# RoverBaseboard.net
KiCad netlist of a schematic drawn in EAGLE
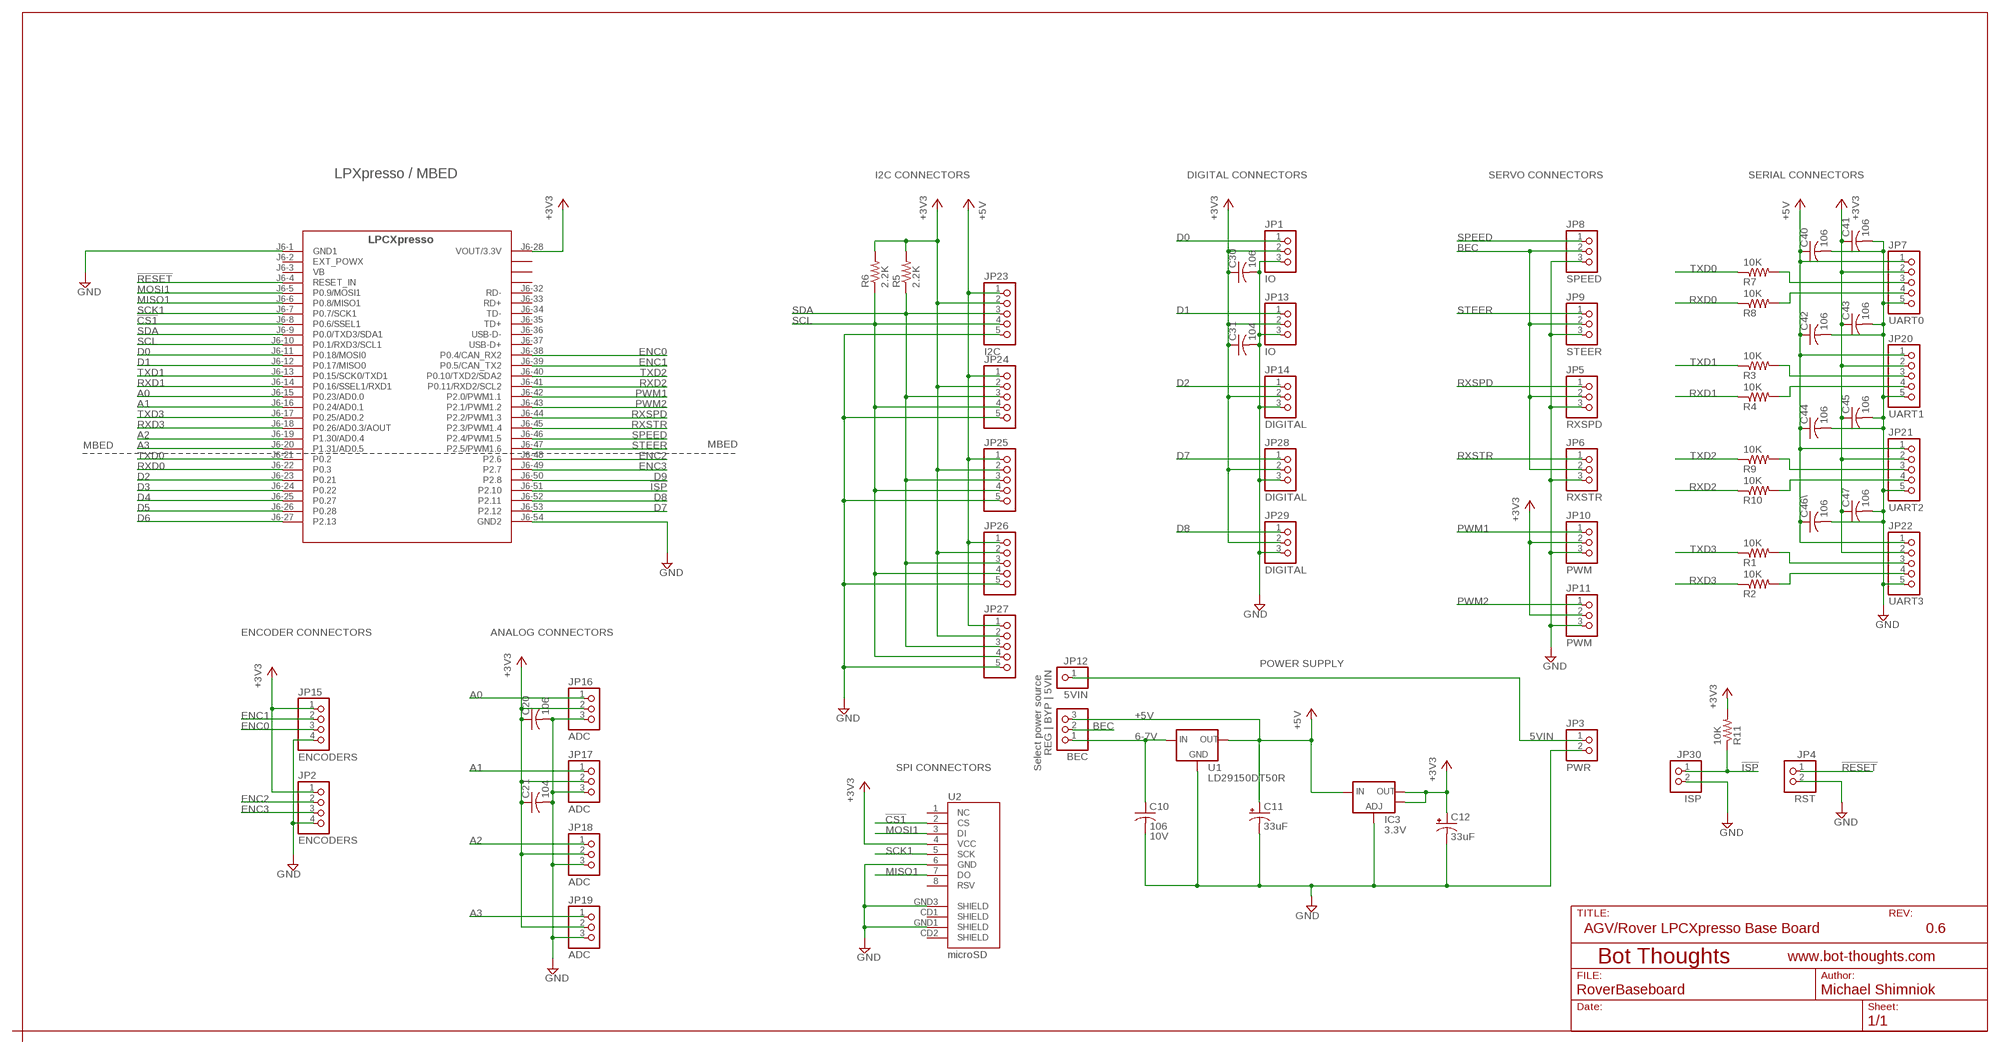
[diagram p0: schematic, sheet 1]

(export (version "E")
  (design (tool "Eeschema 10.0.6"))
  (components
    (comp (ref "BEC")
      (value "REG | BYP | 5VIN")
      (footprint "eagle-import:1X03-S")
      (libsource (lib "eagle-import") (part "PINHD-1X03_2.54-S"))
    )
    (comp (ref "C10")
      (value "106")
      (footprint "eagle-import:C1206")
      (fields (field (name "VOLTAGE") "10V"))
      (libsource (lib "eagle-import") (part "C-USC1206"))
    )
    (comp (ref "C11")
      (value "33uF")
      (footprint "eagle-import:SMC_B")
      (libsource (lib "eagle-import") (part "CPOL-USSMCB"))
    )
    (comp (ref "C12")
      (value "33uF")
      (footprint "eagle-import:SMC_B")
      (libsource (lib "eagle-import") (part "CPOL-USSMCB"))
    )
    (comp (ref "C20")
      (value "106")
      (footprint "eagle-import:C0603")
      (libsource (lib "eagle-import") (part "C-USC0603"))
    )
    (comp (ref "C21")
      (value "104")
      (footprint "eagle-import:C0603")
      (libsource (lib "eagle-import") (part "C-USC0603"))
    )
    (comp (ref "C30")
      (value "106")
      (footprint "eagle-import:C0603")
      (libsource (lib "eagle-import") (part "C-USC0603"))
    )
    (comp (ref "C31")
      (value "104")
      (footprint "eagle-import:C0603")
      (libsource (lib "eagle-import") (part "C-USC0603"))
    )
    (comp (ref "C40")
      (value "106")
      (footprint "eagle-import:C0603")
      (libsource (lib "eagle-import") (part "C-USC0603"))
    )
    (comp (ref "C41")
      (value "106")
      (footprint "eagle-import:C0603")
      (libsource (lib "eagle-import") (part "C-USC0603"))
    )
    (comp (ref "C42")
      (value "106")
      (footprint "eagle-import:C0603")
      (libsource (lib "eagle-import") (part "C-USC0603"))
    )
    (comp (ref "C43")
      (value "106")
      (footprint "eagle-import:C0603")
      (libsource (lib "eagle-import") (part "C-USC0603"))
    )
    (comp (ref "C44")
      (value "106")
      (footprint "eagle-import:C0603")
      (libsource (lib "eagle-import") (part "C-USC0603"))
    )
    (comp (ref "C45")
      (value "106")
      (footprint "eagle-import:C0603")
      (libsource (lib "eagle-import") (part "C-USC0603"))
    )
    (comp (ref "C46\\")
      (value "106")
      (footprint "eagle-import:C0603")
      (libsource (lib "eagle-import") (part "C-USC0603"))
    )
    (comp (ref "C47")
      (value "106")
      (footprint "eagle-import:C0603")
      (libsource (lib "eagle-import") (part "C-USC0603"))
    )
    (comp (ref "IC3")
      (value "3.3V")
      (footprint "eagle-import:SOT223")
      (libsource (lib "eagle-import") (part "V_REG_LM1117SOT223"))
    )
    (comp (ref "JP1")
      (value "IO")
      (footprint "eagle-import:1X03-S")
      (libsource (lib "eagle-import") (part "PINHD-1X03_2.54-S"))
    )
    (comp (ref "JP2")
      (value "ENCODERS")
      (footprint "eagle-import:1X04-S")
      (libsource (lib "eagle-import") (part "PINHD-1X04_2.54-S"))
    )
    (comp (ref "JP3")
      (value "PWR")
      (footprint "eagle-import:1X02-S")
      (libsource (lib "eagle-import") (part "PINHD-1X02_2.54-S"))
    )
    (comp (ref "JP4")
      (value "RST")
      (footprint "eagle-import:1X02-S")
      (libsource (lib "eagle-import") (part "PINHD-1X02_2.54-S"))
    )
    (comp (ref "JP5")
      (value "RXSPD")
      (footprint "eagle-import:1X03-S")
      (libsource (lib "eagle-import") (part "PINHD-1X03_2.54-S"))
    )
    (comp (ref "JP6")
      (value "RXSTR")
      (footprint "eagle-import:1X03-S")
      (libsource (lib "eagle-import") (part "PINHD-1X03_2.54-S"))
    )
    (comp (ref "JP7")
      (value "UART0")
      (footprint "eagle-import:1X05-S")
      (libsource (lib "eagle-import") (part "PINHD-1X05_2.54-S"))
    )
    (comp (ref "JP8")
      (value "SPEED")
      (footprint "eagle-import:1X03-S")
      (libsource (lib "eagle-import") (part "PINHD-1X03_2.54-S"))
    )
    (comp (ref "JP9")
      (value "STEER")
      (footprint "eagle-import:1X03-S")
      (libsource (lib "eagle-import") (part "PINHD-1X03_2.54-S"))
    )
    (comp (ref "JP10")
      (value "PWM")
      (footprint "eagle-import:1X03-S")
      (libsource (lib "eagle-import") (part "PINHD-1X03_2.54-S"))
    )
    (comp (ref "JP11")
      (value "PWM")
      (footprint "eagle-import:1X03-S")
      (libsource (lib "eagle-import") (part "PINHD-1X03_2.54-S"))
    )
    (comp (ref "JP12")
      (value "5VIN")
      (footprint "eagle-import:1X01-S")
      (libsource (lib "eagle-import") (part "PINHD-1X01_2.54-S"))
    )
    (comp (ref "JP13")
      (value "IO")
      (footprint "eagle-import:1X03-S")
      (libsource (lib "eagle-import") (part "PINHD-1X03_2.54-S"))
    )
    (comp (ref "JP14")
      (value "DIGITAL")
      (footprint "eagle-import:1X03-S")
      (libsource (lib "eagle-import") (part "PINHD-1X03_2.54-S"))
    )
    (comp (ref "JP15")
      (value "ENCODERS")
      (footprint "eagle-import:1X04-S")
      (libsource (lib "eagle-import") (part "PINHD-1X04_2.54-S"))
    )
    (comp (ref "JP16")
      (value "ADC")
      (footprint "eagle-import:1X03-S")
      (libsource (lib "eagle-import") (part "PINHD-1X03_2.54-S"))
    )
    (comp (ref "JP17")
      (value "ADC")
      (footprint "eagle-import:1X03-S")
      (libsource (lib "eagle-import") (part "PINHD-1X03_2.54-S"))
    )
    (comp (ref "JP18")
      (value "ADC")
      (footprint "eagle-import:1X03-S")
      (libsource (lib "eagle-import") (part "PINHD-1X03_2.54-S"))
    )
    (comp (ref "JP19")
      (value "ADC")
      (footprint "eagle-import:1X03-S")
      (libsource (lib "eagle-import") (part "PINHD-1X03_2.54-S"))
    )
    (comp (ref "JP20")
      (value "UART1")
      (footprint "eagle-import:1X05-S")
      (libsource (lib "eagle-import") (part "PINHD-1X05_2.54-S"))
    )
    (comp (ref "JP21")
      (value "UART2")
      (footprint "eagle-import:1X05-S")
      (libsource (lib "eagle-import") (part "PINHD-1X05_2.54-S"))
    )
    (comp (ref "JP22")
      (value "UART3")
      (footprint "eagle-import:1X05-S")
      (libsource (lib "eagle-import") (part "PINHD-1X05_2.54-S"))
    )
    (comp (ref "JP23")
      (value "I2C")
      (footprint "eagle-import:1X05-S")
      (libsource (lib "eagle-import") (part "PINHD-1X05_2.54-S"))
    )
    (comp (ref "JP24")
      (value "PINHD-1X05_2.54-S")
      (footprint "eagle-import:1X05-S")
      (libsource (lib "eagle-import") (part "PINHD-1X05_2.54-S"))
    )
    (comp (ref "JP25")
      (value "PINHD-1X05_2.54-S")
      (footprint "eagle-import:1X05-S")
      (libsource (lib "eagle-import") (part "PINHD-1X05_2.54-S"))
    )
    (comp (ref "JP26")
      (value "PINHD-1X05_2.54-S")
      (footprint "eagle-import:1X05-S")
      (libsource (lib "eagle-import") (part "PINHD-1X05_2.54-S"))
    )
    (comp (ref "JP27")
      (value "PINHD-1X05_2.54-S")
      (footprint "eagle-import:1X05-S")
      (libsource (lib "eagle-import") (part "PINHD-1X05_2.54-S"))
    )
    (comp (ref "JP28")
      (value "DIGITAL")
      (footprint "eagle-import:1X03-S")
      (libsource (lib "eagle-import") (part "PINHD-1X03_2.54-S"))
    )
    (comp (ref "JP29")
      (value "DIGITAL")
      (footprint "eagle-import:1X03-S")
      (libsource (lib "eagle-import") (part "PINHD-1X03_2.54-S"))
    )
    (comp (ref "JP30")
      (value "ISP")
      (footprint "eagle-import:1X02-S")
      (libsource (lib "eagle-import") (part "PINHD-1X02_2.54-S"))
    )
    (comp (ref "R1")
      (value "10K")
      (footprint "eagle-import:R0603")
      (fields (field (name "MPN") "WCR0805-220RFI"))
      (libsource (lib "eagle-import") (part "R-US_R0603"))
    )
    (comp (ref "R2")
      (value "10K")
      (footprint "eagle-import:R0603")
      (fields (field (name "MPN") "WCR0805-220RFI"))
      (libsource (lib "eagle-import") (part "R-US_R0603"))
    )
    (comp (ref "R3")
      (value "10K")
      (footprint "eagle-import:R0603")
      (fields (field (name "MPN") "WCR0805-220RFI"))
      (libsource (lib "eagle-import") (part "R-US_R0603"))
    )
    (comp (ref "R4")
      (value "10K")
      (footprint "eagle-import:R0603")
      (fields (field (name "MPN") "WCR0805-220RFI"))
      (libsource (lib "eagle-import") (part "R-US_R0603"))
    )
    (comp (ref "R5")
      (value "2.2K")
      (footprint "eagle-import:R0603")
      (libsource (lib "eagle-import") (part "R-US_R0603"))
    )
    (comp (ref "R6")
      (value "2.2K")
      (footprint "eagle-import:R0603")
      (libsource (lib "eagle-import") (part "R-US_R0603"))
    )
    (comp (ref "R7")
      (value "10K")
      (footprint "eagle-import:R0603")
      (fields (field (name "MPN") "WCR0805-220RFI"))
      (libsource (lib "eagle-import") (part "R-US_R0603"))
    )
    (comp (ref "R8")
      (value "10K")
      (footprint "eagle-import:R0603")
      (fields (field (name "MPN") "WCR0805-220RFI"))
      (libsource (lib "eagle-import") (part "R-US_R0603"))
    )
    (comp (ref "R9")
      (value "10K")
      (footprint "eagle-import:R0603")
      (fields (field (name "MPN") "WCR0805-220RFI"))
      (libsource (lib "eagle-import") (part "R-US_R0603"))
    )
    (comp (ref "R10")
      (value "10K")
      (footprint "eagle-import:R0603")
      (fields (field (name "MPN") "WCR0805-220RFI"))
      (libsource (lib "eagle-import") (part "R-US_R0603"))
    )
    (comp (ref "R11")
      (value "10K")
      (footprint "eagle-import:R0603")
      (fields (field (name "MPN") "WCR0805-220RFI"))
      (libsource (lib "eagle-import") (part "R-US_R0603"))
    )
    (comp (ref "U$1")
      (value "LPCXPRESSO")
      (footprint "eagle-import:LPCXPRESSO_NO_PAD")
      (libsource (lib "eagle-import") (part "LPCXPRESSO_NO_PAD_1768_REVB"))
    )
    (comp (ref "U1")
      (value "LD29150DT50R")
      (footprint "eagle-import:DPAK")
      (libsource (lib "eagle-import") (part "LD29150DT"))
    )
    (comp (ref "U2")
      (value "microSD")
      (footprint "eagle-import:MICRO-SD-SOCKET-PP")
      (libsource (lib "eagle-import") (part "USD-SOCKETNEW"))
    )
  )
  (nets
    (net (code "1") (name "+3V3") (class "Default")
      (node (ref "C12") (pin "+") (pinfunction "+_+") (pintype "passive"))
      (node (ref "C20") (pin "1") (pinfunction "1_1") (pintype "passive"))
      (node (ref "C21") (pin "1") (pinfunction "1_1") (pintype "passive"))
      (node (ref "C30") (pin "1") (pinfunction "1_1") (pintype "passive"))
      (node (ref "C31") (pin "1") (pinfunction "1_1") (pintype "passive"))
      (node (ref "C41") (pin "1") (pinfunction "1_1") (pintype "passive"))
      (node (ref "C43") (pin "1") (pinfunction "1_1") (pintype "passive"))
      (node (ref "C45") (pin "1") (pinfunction "1_1") (pintype "passive"))
      (node (ref "C47") (pin "1") (pinfunction "1_1") (pintype "passive"))
      (node (ref "IC3") (pin "2") (pinfunction "OUT_2") (pintype "output"))
      (node (ref "IC3") (pin "4") (pinfunction "OUT_4") (pintype "output"))
      (node (ref "JP1") (pin "2") (pinfunction "2_2") (pintype "passive"))
      (node (ref "JP10") (pin "2") (pinfunction "2_2") (pintype "passive"))
      (node (ref "JP11") (pin "2") (pinfunction "2_2") (pintype "passive"))
      (node (ref "JP13") (pin "2") (pinfunction "2_2") (pintype "passive"))
      (node (ref "JP14") (pin "2") (pinfunction "2_2") (pintype "passive"))
      (node (ref "JP15") (pin "1") (pinfunction "1_1") (pintype "passive"))
      (node (ref "JP16") (pin "2") (pinfunction "2_2") (pintype "passive"))
      (node (ref "JP17") (pin "2") (pinfunction "2_2") (pintype "passive"))
      (node (ref "JP18") (pin "2") (pinfunction "2_2") (pintype "passive"))
      (node (ref "JP19") (pin "2") (pinfunction "2_2") (pintype "passive"))
      (node (ref "JP2") (pin "1") (pinfunction "1_1") (pintype "passive"))
      (node (ref "JP20") (pin "2") (pinfunction "2_2") (pintype "passive"))
      (node (ref "JP21") (pin "2") (pinfunction "2_2") (pintype "passive"))
      (node (ref "JP22") (pin "2") (pinfunction "2_2") (pintype "passive"))
      (node (ref "JP23") (pin "2") (pinfunction "2_2") (pintype "passive"))
      (node (ref "JP24") (pin "2") (pinfunction "2_2") (pintype "passive"))
      (node (ref "JP25") (pin "2") (pinfunction "2_2") (pintype "passive"))
      (node (ref "JP26") (pin "2") (pinfunction "2_2") (pintype "passive"))
      (node (ref "JP27") (pin "2") (pinfunction "2_2") (pintype "passive"))
      (node (ref "JP28") (pin "2") (pinfunction "2_2") (pintype "passive"))
      (node (ref "JP29") (pin "2") (pinfunction "2_2") (pintype "passive"))
      (node (ref "JP7") (pin "2") (pinfunction "2_2") (pintype "passive"))
      (node (ref "R11") (pin "2") (pinfunction "2_2") (pintype "passive"))
      (node (ref "R5") (pin "2") (pinfunction "2_2") (pintype "passive"))
      (node (ref "R6") (pin "2") (pinfunction "2_2") (pintype "passive"))
      (node (ref "U$1") (pin "J6-28") (pinfunction "VOUT/3.3V_J6-28") (pintype "bidirectional"))
      (node (ref "U2") (pin "4") (pinfunction "VCC_4") (pintype "bidirectional"))
    )
    (net (code "2") (name "+5V") (class "Default")
      (node (ref "BEC") (pin "3") (pinfunction "3_3") (pintype "passive"))
      (node (ref "C11") (pin "+") (pinfunction "+_+") (pintype "passive"))
      (node (ref "C40") (pin "1") (pinfunction "1_1") (pintype "passive"))
      (node (ref "C42") (pin "1") (pinfunction "1_1") (pintype "passive"))
      (node (ref "C44") (pin "1") (pinfunction "1_1") (pintype "passive"))
      (node (ref "C46\\") (pin "1") (pinfunction "1_1") (pintype "passive"))
      (node (ref "IC3") (pin "3") (pinfunction "IN_3") (pintype "input"))
      (node (ref "JP20") (pin "1") (pinfunction "1_1") (pintype "passive"))
      (node (ref "JP21") (pin "1") (pinfunction "1_1") (pintype "passive"))
      (node (ref "JP22") (pin "1") (pinfunction "1_1") (pintype "passive"))
      (node (ref "JP23") (pin "1") (pinfunction "1_1") (pintype "passive"))
      (node (ref "JP24") (pin "1") (pinfunction "1_1") (pintype "passive"))
      (node (ref "JP25") (pin "1") (pinfunction "1_1") (pintype "passive"))
      (node (ref "JP26") (pin "1") (pinfunction "1_1") (pintype "passive"))
      (node (ref "JP27") (pin "1") (pinfunction "1_1") (pintype "passive"))
      (node (ref "JP7") (pin "1") (pinfunction "1_1") (pintype "passive"))
      (node (ref "U1") (pin "3") (pinfunction "VOUT_3") (pintype "bidirectional"))
    )
    (net (code "3") (name "/5VIN") (class "Default")
      (node (ref "JP12") (pin "1") (pinfunction "1_1") (pintype "passive"))
      (node (ref "JP3") (pin "1") (pinfunction "1_1") (pintype "passive"))
    )
    (net (code "4") (name "/6-7V") (class "Default")
      (node (ref "BEC") (pin "1") (pinfunction "1_1") (pintype "passive"))
      (node (ref "C10") (pin "1") (pinfunction "1_1") (pintype "passive"))
      (node (ref "U1") (pin "1") (pinfunction "VIN_1") (pintype "bidirectional"))
    )
    (net (code "5") (name "/A0") (class "Default")
      (node (ref "JP16") (pin "1") (pinfunction "1_1") (pintype "passive"))
      (node (ref "U$1") (pin "J6-15") (pinfunction "P0.23/AD0.0_J6-15") (pintype "bidirectional"))
    )
    (net (code "6") (name "/A1") (class "Default")
      (node (ref "JP17") (pin "1") (pinfunction "1_1") (pintype "passive"))
      (node (ref "U$1") (pin "J6-16") (pinfunction "P0.24/AD0.1_J6-16") (pintype "bidirectional"))
    )
    (net (code "7") (name "/A2") (class "Default")
      (node (ref "JP18") (pin "1") (pinfunction "1_1") (pintype "passive"))
      (node (ref "U$1") (pin "J6-19") (pinfunction "P1.30/AD0.4_J6-19") (pintype "bidirectional"))
    )
    (net (code "8") (name "/A3") (class "Default")
      (node (ref "JP19") (pin "1") (pinfunction "1_1") (pintype "passive"))
      (node (ref "U$1") (pin "J6-20") (pinfunction "P1.31/AD0.5_J6-20") (pintype "bidirectional"))
    )
    (net (code "9") (name "/BEC") (class "Default")
      (node (ref "BEC") (pin "2") (pinfunction "2_2") (pintype "passive"))
      (node (ref "JP5") (pin "2") (pinfunction "2_2") (pintype "passive"))
      (node (ref "JP6") (pin "2") (pinfunction "2_2") (pintype "passive"))
      (node (ref "JP8") (pin "2") (pinfunction "2_2") (pintype "passive"))
      (node (ref "JP9") (pin "2") (pinfunction "2_2") (pintype "passive"))
    )
    (net (code "10") (name "/D0") (class "Default")
      (node (ref "JP1") (pin "1") (pinfunction "1_1") (pintype "passive"))
      (node (ref "U$1") (pin "J6-11") (pinfunction "P0.18/MOSI0_J6-11") (pintype "bidirectional"))
    )
    (net (code "11") (name "/D1") (class "Default")
      (node (ref "JP13") (pin "1") (pinfunction "1_1") (pintype "passive"))
      (node (ref "U$1") (pin "J6-12") (pinfunction "P0.17/MISO0_J6-12") (pintype "bidirectional"))
    )
    (net (code "12") (name "/D2") (class "Default")
      (node (ref "JP14") (pin "1") (pinfunction "1_1") (pintype "passive"))
      (node (ref "U$1") (pin "J6-23") (pinfunction "P0.21_J6-23") (pintype "bidirectional"))
    )
    (net (code "13") (name "/D3") (class "Default")
      (node (ref "U$1") (pin "J6-24") (pinfunction "P0.22_J6-24") (pintype "bidirectional"))
    )
    (net (code "14") (name "/D4") (class "Default")
      (node (ref "U$1") (pin "J6-25") (pinfunction "P0.27_J6-25") (pintype "bidirectional"))
    )
    (net (code "15") (name "/D5") (class "Default")
      (node (ref "U$1") (pin "J6-26") (pinfunction "P0.28_J6-26") (pintype "bidirectional"))
    )
    (net (code "16") (name "/D6") (class "Default")
      (node (ref "U$1") (pin "J6-27") (pinfunction "P2.13_J6-27") (pintype "bidirectional"))
    )
    (net (code "17") (name "/D7") (class "Default")
      (node (ref "JP28") (pin "1") (pinfunction "1_1") (pintype "passive"))
      (node (ref "U$1") (pin "J6-53") (pinfunction "P2.12_J6-53") (pintype "bidirectional"))
    )
    (net (code "18") (name "/D8") (class "Default")
      (node (ref "JP29") (pin "1") (pinfunction "1_1") (pintype "passive"))
      (node (ref "U$1") (pin "J6-52") (pinfunction "P2.11_J6-52") (pintype "bidirectional"))
    )
    (net (code "19") (name "/D9") (class "Default")
      (node (ref "U$1") (pin "J6-50") (pinfunction "P2.8_J6-50") (pintype "bidirectional"))
    )
    (net (code "20") (name "/ENC0") (class "Default")
      (node (ref "JP15") (pin "3") (pinfunction "3_3") (pintype "passive"))
      (node (ref "U$1") (pin "J6-38") (pinfunction "P0.4/CAN_RX2_J6-38") (pintype "bidirectional"))
    )
    (net (code "21") (name "/ENC1") (class "Default")
      (node (ref "JP15") (pin "2") (pinfunction "2_2") (pintype "passive"))
      (node (ref "U$1") (pin "J6-39") (pinfunction "P0.5/CAN_TX2_J6-39") (pintype "bidirectional"))
    )
    (net (code "22") (name "/ENC2") (class "Default")
      (node (ref "JP2") (pin "2") (pinfunction "2_2") (pintype "passive"))
      (node (ref "U$1") (pin "J6-48") (pinfunction "P2.6_J6-48") (pintype "bidirectional"))
    )
    (net (code "23") (name "/ENC3") (class "Default")
      (node (ref "JP2") (pin "3") (pinfunction "3_3") (pintype "passive"))
      (node (ref "U$1") (pin "J6-49") (pinfunction "P2.7_J6-49") (pintype "bidirectional"))
    )
    (net (code "24") (name "/MISO1") (class "Default")
      (node (ref "U$1") (pin "J6-6") (pinfunction "P0.8/MISO1_J6-6") (pintype "bidirectional"))
      (node (ref "U2") (pin "7") (pinfunction "DO_7") (pintype "bidirectional"))
    )
    (net (code "25") (name "/MOSI1") (class "Default")
      (node (ref "U$1") (pin "J6-5") (pinfunction "P0.9/MOSI1_J6-5") (pintype "bidirectional"))
      (node (ref "U2") (pin "3") (pinfunction "DI_3") (pintype "bidirectional"))
    )
    (net (code "26") (name "/PWM1") (class "Default")
      (node (ref "JP10") (pin "1") (pinfunction "1_1") (pintype "passive"))
      (node (ref "U$1") (pin "J6-42") (pinfunction "P2.0/PWM1.1_J6-42") (pintype "bidirectional"))
    )
    (net (code "27") (name "/PWM2") (class "Default")
      (node (ref "JP11") (pin "1") (pinfunction "1_1") (pintype "passive"))
      (node (ref "U$1") (pin "J6-43") (pinfunction "P2.1/PWM1.2_J6-43") (pintype "bidirectional"))
    )
    (net (code "28") (name "/RXD0") (class "Default")
      (node (ref "R8") (pin "1") (pinfunction "1_1") (pintype "passive"))
      (node (ref "U$1") (pin "J6-22") (pinfunction "P0.3_J6-22") (pintype "bidirectional"))
    )
    (net (code "29") (name "/RXD1") (class "Default")
      (node (ref "R4") (pin "1") (pinfunction "1_1") (pintype "passive"))
      (node (ref "U$1") (pin "J6-14") (pinfunction "P0.16/SSEL1/RXD1_J6-14") (pintype "bidirectional"))
    )
    (net (code "30") (name "/RXD2") (class "Default")
      (node (ref "R10") (pin "1") (pinfunction "1_1") (pintype "passive"))
      (node (ref "U$1") (pin "J6-41") (pinfunction "P0.11/RXD2/SCL2_J6-41") (pintype "bidirectional"))
    )
    (net (code "31") (name "/RXD3") (class "Default")
      (node (ref "R2") (pin "1") (pinfunction "1_1") (pintype "passive"))
      (node (ref "U$1") (pin "J6-18") (pinfunction "P0.26/AD0.3/AOUT_J6-18") (pintype "bidirectional"))
    )
    (net (code "32") (name "/RXSPD") (class "Default")
      (node (ref "JP5") (pin "1") (pinfunction "1_1") (pintype "passive"))
      (node (ref "U$1") (pin "J6-44") (pinfunction "P2.2/PWM1.3_J6-44") (pintype "bidirectional"))
    )
    (net (code "33") (name "/RXSTR") (class "Default")
      (node (ref "JP6") (pin "1") (pinfunction "1_1") (pintype "passive"))
      (node (ref "U$1") (pin "J6-45") (pinfunction "P2.3/PWM1.4_J6-45") (pintype "bidirectional"))
    )
    (net (code "34") (name "/SCK1") (class "Default")
      (node (ref "U$1") (pin "J6-7") (pinfunction "P0.7/SCK1_J6-7") (pintype "bidirectional"))
      (node (ref "U2") (pin "5") (pinfunction "SCK_5") (pintype "bidirectional"))
    )
    (net (code "35") (name "/SCL") (class "Default")
      (node (ref "JP23") (pin "4") (pinfunction "4_4") (pintype "passive"))
      (node (ref "JP24") (pin "4") (pinfunction "4_4") (pintype "passive"))
      (node (ref "JP25") (pin "4") (pinfunction "4_4") (pintype "passive"))
      (node (ref "JP26") (pin "4") (pinfunction "4_4") (pintype "passive"))
      (node (ref "JP27") (pin "4") (pinfunction "4_4") (pintype "passive"))
      (node (ref "R6") (pin "1") (pinfunction "1_1") (pintype "passive"))
      (node (ref "U$1") (pin "J6-10") (pinfunction "P0.1/RXD3/SCL1_J6-10") (pintype "bidirectional"))
    )
    (net (code "36") (name "/SDA") (class "Default")
      (node (ref "JP23") (pin "3") (pinfunction "3_3") (pintype "passive"))
      (node (ref "JP24") (pin "3") (pinfunction "3_3") (pintype "passive"))
      (node (ref "JP25") (pin "3") (pinfunction "3_3") (pintype "passive"))
      (node (ref "JP26") (pin "3") (pinfunction "3_3") (pintype "passive"))
      (node (ref "JP27") (pin "3") (pinfunction "3_3") (pintype "passive"))
      (node (ref "R5") (pin "1") (pinfunction "1_1") (pintype "passive"))
      (node (ref "U$1") (pin "J6-9") (pinfunction "P0.0/TXD3/SDA1_J6-9") (pintype "bidirectional"))
    )
    (net (code "37") (name "/SPEED") (class "Default")
      (node (ref "JP8") (pin "1") (pinfunction "1_1") (pintype "passive"))
      (node (ref "U$1") (pin "J6-46") (pinfunction "P2.4/PWM1.5_J6-46") (pintype "bidirectional"))
    )
    (net (code "38") (name "/STEER") (class "Default")
      (node (ref "JP9") (pin "1") (pinfunction "1_1") (pintype "passive"))
      (node (ref "U$1") (pin "J6-47") (pinfunction "P2.5/PWM1.6_J6-47") (pintype "bidirectional"))
    )
    (net (code "39") (name "/TXD0") (class "Default")
      (node (ref "R7") (pin "1") (pinfunction "1_1") (pintype "passive"))
      (node (ref "U$1") (pin "J6-21") (pinfunction "P0.2_J6-21") (pintype "bidirectional"))
    )
    (net (code "40") (name "/TXD1") (class "Default")
      (node (ref "R3") (pin "1") (pinfunction "1_1") (pintype "passive"))
      (node (ref "U$1") (pin "J6-13") (pinfunction "P0.15/SCK0/TXD1_J6-13") (pintype "bidirectional"))
    )
    (net (code "41") (name "/TXD2") (class "Default")
      (node (ref "R9") (pin "1") (pinfunction "1_1") (pintype "passive"))
      (node (ref "U$1") (pin "J6-40") (pinfunction "P0.10/TXD2/SDA2_J6-40") (pintype "bidirectional"))
    )
    (net (code "42") (name "/TXD3") (class "Default")
      (node (ref "R1") (pin "1") (pinfunction "1_1") (pintype "passive"))
      (node (ref "U$1") (pin "J6-17") (pinfunction "P0.25/AD0.2_J6-17") (pintype "bidirectional"))
    )
    (net (code "43") (name "/~{CS1}") (class "Default")
      (node (ref "U$1") (pin "J6-8") (pinfunction "P0.6/SSEL1_J6-8") (pintype "bidirectional"))
      (node (ref "U2") (pin "2") (pinfunction "CS_2") (pintype "bidirectional"))
    )
    (net (code "44") (name "/~{ISP}") (class "Default")
      (node (ref "JP30") (pin "1") (pinfunction "1_1") (pintype "passive"))
      (node (ref "R11") (pin "1") (pinfunction "1_1") (pintype "passive"))
      (node (ref "U$1") (pin "J6-51") (pinfunction "P2.10_J6-51") (pintype "bidirectional"))
    )
    (net (code "45") (name "/~{RESET}") (class "Default")
      (node (ref "JP4") (pin "1") (pinfunction "1_1") (pintype "passive"))
      (node (ref "U$1") (pin "J6-4") (pinfunction "RESET_IN_J6-4") (pintype "bidirectional"))
    )
    (net (code "46") (name "GND") (class "Default")
      (node (ref "C10") (pin "2") (pinfunction "2_2") (pintype "passive"))
      (node (ref "C11") (pin "-") (pinfunction "-_-") (pintype "passive"))
      (node (ref "C12") (pin "-") (pinfunction "-_-") (pintype "passive"))
      (node (ref "C20") (pin "2") (pinfunction "2_2") (pintype "passive"))
      (node (ref "C21") (pin "2") (pinfunction "2_2") (pintype "passive"))
      (node (ref "C30") (pin "2") (pinfunction "2_2") (pintype "passive"))
      (node (ref "C31") (pin "2") (pinfunction "2_2") (pintype "passive"))
      (node (ref "C40") (pin "2") (pinfunction "2_2") (pintype "passive"))
      (node (ref "C41") (pin "2") (pinfunction "2_2") (pintype "passive"))
      (node (ref "C42") (pin "2") (pinfunction "2_2") (pintype "passive"))
      (node (ref "C43") (pin "2") (pinfunction "2_2") (pintype "passive"))
      (node (ref "C44") (pin "2") (pinfunction "2_2") (pintype "passive"))
      (node (ref "C45") (pin "2") (pinfunction "2_2") (pintype "passive"))
      (node (ref "C46\\") (pin "2") (pinfunction "2_2") (pintype "passive"))
      (node (ref "C47") (pin "2") (pinfunction "2_2") (pintype "passive"))
      (node (ref "IC3") (pin "1") (pinfunction "ADJ_1") (pintype "input"))
      (node (ref "JP1") (pin "3") (pinfunction "3_3") (pintype "passive"))
      (node (ref "JP10") (pin "3") (pinfunction "3_3") (pintype "passive"))
      (node (ref "JP11") (pin "3") (pinfunction "3_3") (pintype "passive"))
      (node (ref "JP13") (pin "3") (pinfunction "3_3") (pintype "passive"))
      (node (ref "JP14") (pin "3") (pinfunction "3_3") (pintype "passive"))
      (node (ref "JP15") (pin "4") (pinfunction "4_4") (pintype "passive"))
      (node (ref "JP16") (pin "3") (pinfunction "3_3") (pintype "passive"))
      (node (ref "JP17") (pin "3") (pinfunction "3_3") (pintype "passive"))
      (node (ref "JP18") (pin "3") (pinfunction "3_3") (pintype "passive"))
      (node (ref "JP19") (pin "3") (pinfunction "3_3") (pintype "passive"))
      (node (ref "JP2") (pin "4") (pinfunction "4_4") (pintype "passive"))
      (node (ref "JP20") (pin "5") (pinfunction "5_5") (pintype "passive"))
      (node (ref "JP21") (pin "5") (pinfunction "5_5") (pintype "passive"))
      (node (ref "JP22") (pin "5") (pinfunction "5_5") (pintype "passive"))
      (node (ref "JP23") (pin "5") (pinfunction "5_5") (pintype "passive"))
      (node (ref "JP24") (pin "5") (pinfunction "5_5") (pintype "passive"))
      (node (ref "JP25") (pin "5") (pinfunction "5_5") (pintype "passive"))
      (node (ref "JP26") (pin "5") (pinfunction "5_5") (pintype "passive"))
      (node (ref "JP27") (pin "5") (pinfunction "5_5") (pintype "passive"))
      (node (ref "JP28") (pin "3") (pinfunction "3_3") (pintype "passive"))
      (node (ref "JP29") (pin "3") (pinfunction "3_3") (pintype "passive"))
      (node (ref "JP3") (pin "2") (pinfunction "2_2") (pintype "passive"))
      (node (ref "JP30") (pin "2") (pinfunction "2_2") (pintype "passive"))
      (node (ref "JP4") (pin "2") (pinfunction "2_2") (pintype "passive"))
      (node (ref "JP5") (pin "3") (pinfunction "3_3") (pintype "passive"))
      (node (ref "JP6") (pin "3") (pinfunction "3_3") (pintype "passive"))
      (node (ref "JP7") (pin "5") (pinfunction "5_5") (pintype "passive"))
      (node (ref "JP8") (pin "3") (pinfunction "3_3") (pintype "passive"))
      (node (ref "JP9") (pin "3") (pinfunction "3_3") (pintype "passive"))
      (node (ref "U$1") (pin "J6-1") (pinfunction "GND1_J6-1") (pintype "bidirectional"))
      (node (ref "U$1") (pin "J6-54") (pinfunction "GND2_J6-54") (pintype "bidirectional"))
      (node (ref "U1") (pin "4") (pinfunction "GND_4") (pintype "bidirectional"))
      (node (ref "U2") (pin "6") (pinfunction "GND_6") (pintype "bidirectional"))
      (node (ref "U2") (pin "GND1") (pinfunction "SHIELD_GND1") (pintype "bidirectional"))
      (node (ref "U2") (pin "GND3") (pinfunction "SHIELD_GND3") (pintype "bidirectional"))
    )
    (net (code "47") (name "Net-(JP7-Pad3)") (class "Default")
      (node (ref "JP7") (pin "3") (pinfunction "3_3") (pintype "passive"))
      (node (ref "R7") (pin "2") (pinfunction "2_2") (pintype "passive"))
    )
    (net (code "48") (name "Net-(JP7-Pad4)") (class "Default")
      (node (ref "JP7") (pin "4") (pinfunction "4_4") (pintype "passive"))
      (node (ref "R8") (pin "2") (pinfunction "2_2") (pintype "passive"))
    )
    (net (code "49") (name "Net-(JP20-Pad3)") (class "Default")
      (node (ref "JP20") (pin "3") (pinfunction "3_3") (pintype "passive"))
      (node (ref "R3") (pin "2") (pinfunction "2_2") (pintype "passive"))
    )
    (net (code "50") (name "Net-(JP20-Pad4)") (class "Default")
      (node (ref "JP20") (pin "4") (pinfunction "4_4") (pintype "passive"))
      (node (ref "R4") (pin "2") (pinfunction "2_2") (pintype "passive"))
    )
    (net (code "51") (name "Net-(JP21-Pad3)") (class "Default")
      (node (ref "JP21") (pin "3") (pinfunction "3_3") (pintype "passive"))
      (node (ref "R9") (pin "2") (pinfunction "2_2") (pintype "passive"))
    )
    (net (code "52") (name "Net-(JP21-Pad4)") (class "Default")
      (node (ref "JP21") (pin "4") (pinfunction "4_4") (pintype "passive"))
      (node (ref "R10") (pin "2") (pinfunction "2_2") (pintype "passive"))
    )
    (net (code "53") (name "Net-(JP22-Pad3)") (class "Default")
      (node (ref "JP22") (pin "3") (pinfunction "3_3") (pintype "passive"))
      (node (ref "R1") (pin "2") (pinfunction "2_2") (pintype "passive"))
    )
    (net (code "54") (name "Net-(JP22-Pad4)") (class "Default")
      (node (ref "JP22") (pin "4") (pinfunction "4_4") (pintype "passive"))
      (node (ref "R2") (pin "2") (pinfunction "2_2") (pintype "passive"))
    )
    (net (code "55") (name "unconnected-(U$1-EXT_POWX-PadJ6-2)") (class "Default")
      (node (ref "U$1") (pin "J6-2") (pinfunction "EXT_POWX_J6-2") (pintype "bidirectional"))
    )
    (net (code "56") (name "unconnected-(U$1-P$24-PadJ6-29)") (class "Default")
      (node (ref "U$1") (pin "J6-29") (pinfunction "P$24_J6-29") (pintype "no_connect"))
    )
    (net (code "57") (name "unconnected-(U$1-P$25-PadJ6-30)") (class "Default")
      (node (ref "U$1") (pin "J6-30") (pinfunction "P$25_J6-30") (pintype "no_connect"))
    )
    (net (code "58") (name "unconnected-(U$1-P$26-PadJ6-31)") (class "Default")
      (node (ref "U$1") (pin "J6-31") (pinfunction "P$26_J6-31") (pintype "no_connect"))
    )
    (net (code "59") (name "unconnected-(U$1-RD+-PadJ6-33)") (class "Default")
      (node (ref "U$1") (pin "J6-33") (pinfunction "RD+_J6-33") (pintype "bidirectional"))
    )
    (net (code "60") (name "unconnected-(U$1-RD--PadJ6-32)") (class "Default")
      (node (ref "U$1") (pin "J6-32") (pinfunction "RD-_J6-32") (pintype "bidirectional"))
    )
    (net (code "61") (name "unconnected-(U$1-TD+-PadJ6-35)") (class "Default")
      (node (ref "U$1") (pin "J6-35") (pinfunction "TD+_J6-35") (pintype "bidirectional"))
    )
    (net (code "62") (name "unconnected-(U$1-TD--PadJ6-34)") (class "Default")
      (node (ref "U$1") (pin "J6-34") (pinfunction "TD-_J6-34") (pintype "bidirectional"))
    )
    (net (code "63") (name "unconnected-(U$1-USB-D+-PadJ6-37)") (class "Default")
      (node (ref "U$1") (pin "J6-37") (pinfunction "USB-D+_J6-37") (pintype "bidirectional"))
    )
    (net (code "64") (name "unconnected-(U$1-USB-D--PadJ6-36)") (class "Default")
      (node (ref "U$1") (pin "J6-36") (pinfunction "USB-D-_J6-36") (pintype "bidirectional"))
    )
    (net (code "65") (name "unconnected-(U$1-VB-PadJ6-3)") (class "Default")
      (node (ref "U$1") (pin "J6-3") (pinfunction "VB_J6-3") (pintype "bidirectional"))
    )
    (net (code "66") (name "unconnected-(U2-NC-Pad1)") (class "Default")
      (node (ref "U2") (pin "1") (pinfunction "NC_1") (pintype "bidirectional"))
    )
    (net (code "67") (name "unconnected-(U2-RSV-Pad8)") (class "Default")
      (node (ref "U2") (pin "8") (pinfunction "RSV_8") (pintype "bidirectional"))
    )
    (net (code "68") (name "unconnected-(U2-SHIELD-PadCD1)") (class "Default")
      (node (ref "U2") (pin "CD1") (pinfunction "SHIELD_CD1") (pintype "bidirectional"))
    )
    (net (code "69") (name "unconnected-(U2-SHIELD-PadCD2)") (class "Default")
      (node (ref "U2") (pin "CD2") (pinfunction "SHIELD_CD2") (pintype "bidirectional"))
    )
  )
)
